# Breadboard.net
KiCad netlist of a schematic drawn in EAGLE
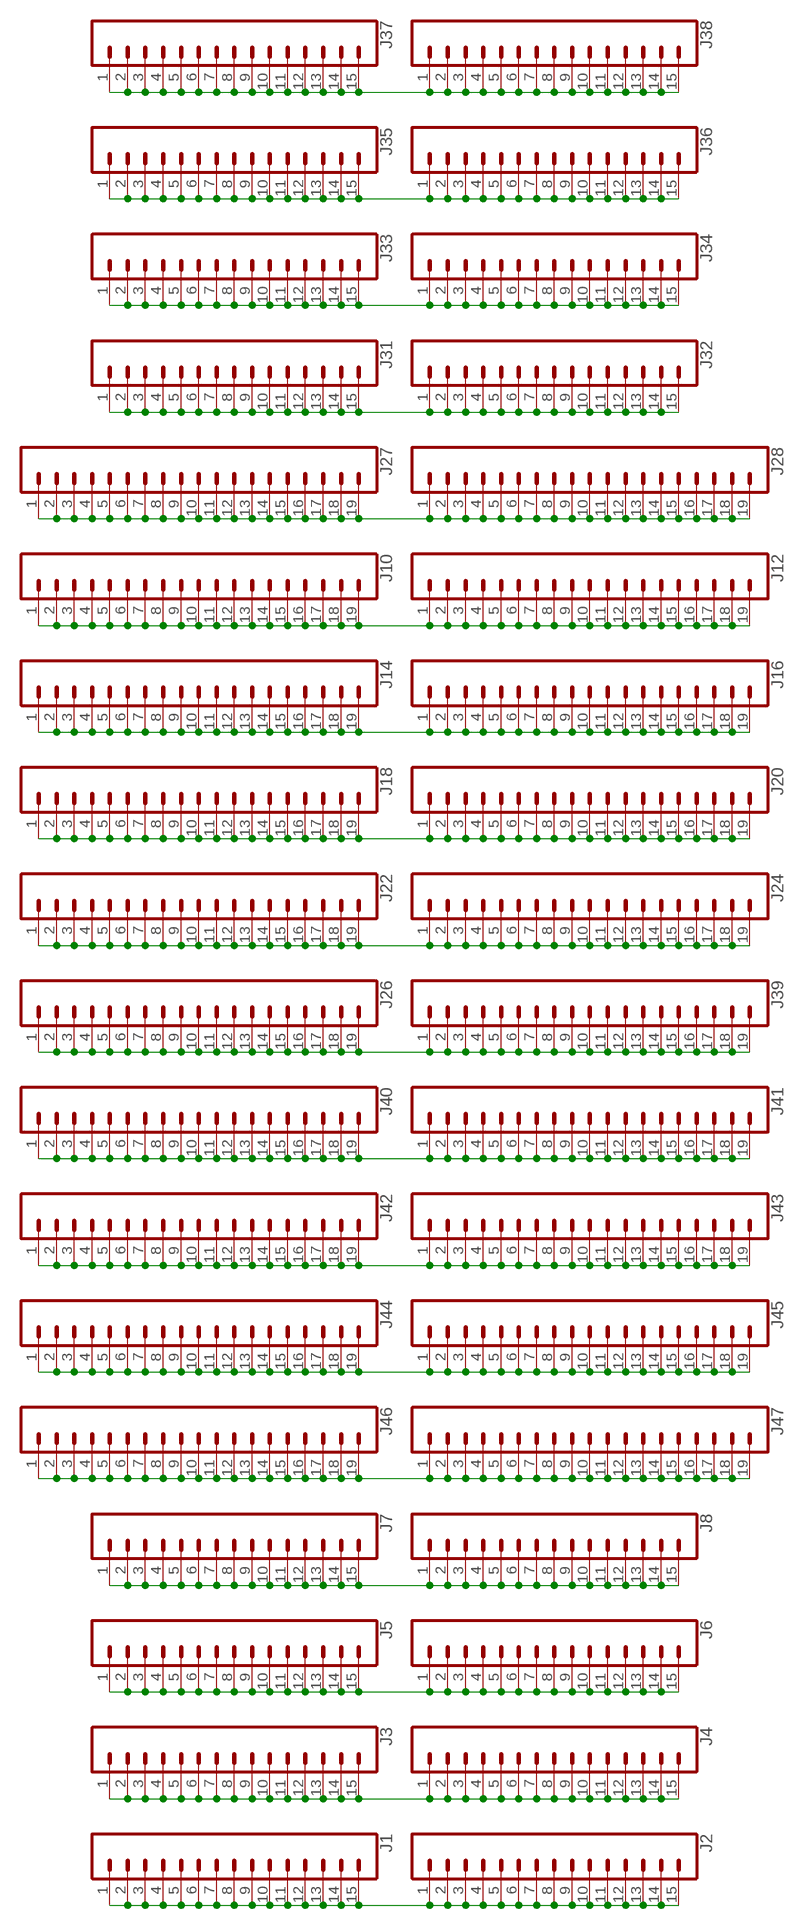
[diagram p0: schematic, sheet 1]

(export (version "E")
  (design (tool "Eeschema 10.0.6"))
  (components
    (comp (ref "J1")
      (value "CONN_15")
      (footprint "eagle-import:1X15")
      (libsource (lib "eagle-import") (part "CONN_15"))
    )
    (comp (ref "J2")
      (value "CONN_15")
      (footprint "eagle-import:1X15")
      (libsource (lib "eagle-import") (part "CONN_15"))
    )
    (comp (ref "J3")
      (value "CONN_15")
      (footprint "eagle-import:1X15")
      (libsource (lib "eagle-import") (part "CONN_15"))
    )
    (comp (ref "J4")
      (value "CONN_15")
      (footprint "eagle-import:1X15")
      (libsource (lib "eagle-import") (part "CONN_15"))
    )
    (comp (ref "J5")
      (value "CONN_15")
      (footprint "eagle-import:1X15")
      (libsource (lib "eagle-import") (part "CONN_15"))
    )
    (comp (ref "J6")
      (value "CONN_15")
      (footprint "eagle-import:1X15")
      (libsource (lib "eagle-import") (part "CONN_15"))
    )
    (comp (ref "J7")
      (value "CONN_15")
      (footprint "eagle-import:1X15")
      (libsource (lib "eagle-import") (part "CONN_15"))
    )
    (comp (ref "J8")
      (value "CONN_15")
      (footprint "eagle-import:1X15")
      (libsource (lib "eagle-import") (part "CONN_15"))
    )
    (comp (ref "J10")
      (value "CONN_19")
      (footprint "eagle-import:1X19")
      (libsource (lib "eagle-import") (part "CONN_19"))
    )
    (comp (ref "J12")
      (value "CONN_19")
      (footprint "eagle-import:1X19")
      (libsource (lib "eagle-import") (part "CONN_19"))
    )
    (comp (ref "J14")
      (value "CONN_19")
      (footprint "eagle-import:1X19")
      (libsource (lib "eagle-import") (part "CONN_19"))
    )
    (comp (ref "J16")
      (value "CONN_19")
      (footprint "eagle-import:1X19")
      (libsource (lib "eagle-import") (part "CONN_19"))
    )
    (comp (ref "J18")
      (value "CONN_19")
      (footprint "eagle-import:1X19")
      (libsource (lib "eagle-import") (part "CONN_19"))
    )
    (comp (ref "J20")
      (value "CONN_19")
      (footprint "eagle-import:1X19")
      (libsource (lib "eagle-import") (part "CONN_19"))
    )
    (comp (ref "J22")
      (value "CONN_19")
      (footprint "eagle-import:1X19")
      (libsource (lib "eagle-import") (part "CONN_19"))
    )
    (comp (ref "J24")
      (value "CONN_19")
      (footprint "eagle-import:1X19")
      (libsource (lib "eagle-import") (part "CONN_19"))
    )
    (comp (ref "J26")
      (value "CONN_19")
      (footprint "eagle-import:1X19")
      (libsource (lib "eagle-import") (part "CONN_19"))
    )
    (comp (ref "J27")
      (value "CONN_19")
      (footprint "eagle-import:1X19")
      (libsource (lib "eagle-import") (part "CONN_19"))
    )
    (comp (ref "J28")
      (value "CONN_19")
      (footprint "eagle-import:1X19")
      (libsource (lib "eagle-import") (part "CONN_19"))
    )
    (comp (ref "J31")
      (value "CONN_15")
      (footprint "eagle-import:1X15")
      (libsource (lib "eagle-import") (part "CONN_15"))
    )
    (comp (ref "J32")
      (value "CONN_15")
      (footprint "eagle-import:1X15")
      (libsource (lib "eagle-import") (part "CONN_15"))
    )
    (comp (ref "J33")
      (value "CONN_15")
      (footprint "eagle-import:1X15")
      (libsource (lib "eagle-import") (part "CONN_15"))
    )
    (comp (ref "J34")
      (value "CONN_15")
      (footprint "eagle-import:1X15")
      (libsource (lib "eagle-import") (part "CONN_15"))
    )
    (comp (ref "J35")
      (value "CONN_15")
      (footprint "eagle-import:1X15")
      (libsource (lib "eagle-import") (part "CONN_15"))
    )
    (comp (ref "J36")
      (value "CONN_15")
      (footprint "eagle-import:1X15")
      (libsource (lib "eagle-import") (part "CONN_15"))
    )
    (comp (ref "J37")
      (value "CONN_15")
      (footprint "eagle-import:1X15")
      (libsource (lib "eagle-import") (part "CONN_15"))
    )
    (comp (ref "J38")
      (value "CONN_15")
      (footprint "eagle-import:1X15")
      (libsource (lib "eagle-import") (part "CONN_15"))
    )
    (comp (ref "J39")
      (value "CONN_19")
      (footprint "eagle-import:1X19")
      (libsource (lib "eagle-import") (part "CONN_19"))
    )
    (comp (ref "J40")
      (value "CONN_19")
      (footprint "eagle-import:1X19")
      (libsource (lib "eagle-import") (part "CONN_19"))
    )
    (comp (ref "J41")
      (value "CONN_19")
      (footprint "eagle-import:1X19")
      (libsource (lib "eagle-import") (part "CONN_19"))
    )
    (comp (ref "J42")
      (value "CONN_19")
      (footprint "eagle-import:1X19")
      (libsource (lib "eagle-import") (part "CONN_19"))
    )
    (comp (ref "J43")
      (value "CONN_19")
      (footprint "eagle-import:1X19")
      (libsource (lib "eagle-import") (part "CONN_19"))
    )
    (comp (ref "J44")
      (value "CONN_19")
      (footprint "eagle-import:1X19")
      (libsource (lib "eagle-import") (part "CONN_19"))
    )
    (comp (ref "J45")
      (value "CONN_19")
      (footprint "eagle-import:1X19")
      (libsource (lib "eagle-import") (part "CONN_19"))
    )
    (comp (ref "J46")
      (value "CONN_19")
      (footprint "eagle-import:1X19")
      (libsource (lib "eagle-import") (part "CONN_19"))
    )
    (comp (ref "J47")
      (value "CONN_19")
      (footprint "eagle-import:1X19")
      (libsource (lib "eagle-import") (part "CONN_19"))
    )
  )
  (nets
    (net (code "1") (name "Net-(J1-Pad1)") (class "Default")
      (node (ref "J1") (pin "1") (pinfunction "1_1") (pintype "passive"))
      (node (ref "J1") (pin "10") (pinfunction "10_10") (pintype "passive"))
      (node (ref "J1") (pin "11") (pinfunction "11_11") (pintype "passive"))
      (node (ref "J1") (pin "12") (pinfunction "12_12") (pintype "passive"))
      (node (ref "J1") (pin "13") (pinfunction "13_13") (pintype "passive"))
      (node (ref "J1") (pin "14") (pinfunction "14_14") (pintype "passive"))
      (node (ref "J1") (pin "15") (pinfunction "15_15") (pintype "passive"))
      (node (ref "J1") (pin "2") (pinfunction "2_2") (pintype "passive"))
      (node (ref "J1") (pin "3") (pinfunction "3_3") (pintype "passive"))
      (node (ref "J1") (pin "4") (pinfunction "4_4") (pintype "passive"))
      (node (ref "J1") (pin "5") (pinfunction "5_5") (pintype "passive"))
      (node (ref "J1") (pin "6") (pinfunction "6_6") (pintype "passive"))
      (node (ref "J1") (pin "7") (pinfunction "7_7") (pintype "passive"))
      (node (ref "J1") (pin "8") (pinfunction "8_8") (pintype "passive"))
      (node (ref "J1") (pin "9") (pinfunction "9_9") (pintype "passive"))
      (node (ref "J2") (pin "1") (pinfunction "1_1") (pintype "passive"))
      (node (ref "J2") (pin "10") (pinfunction "10_10") (pintype "passive"))
      (node (ref "J2") (pin "11") (pinfunction "11_11") (pintype "passive"))
      (node (ref "J2") (pin "12") (pinfunction "12_12") (pintype "passive"))
      (node (ref "J2") (pin "13") (pinfunction "13_13") (pintype "passive"))
      (node (ref "J2") (pin "14") (pinfunction "14_14") (pintype "passive"))
      (node (ref "J2") (pin "15") (pinfunction "15_15") (pintype "passive"))
      (node (ref "J2") (pin "2") (pinfunction "2_2") (pintype "passive"))
      (node (ref "J2") (pin "3") (pinfunction "3_3") (pintype "passive"))
      (node (ref "J2") (pin "4") (pinfunction "4_4") (pintype "passive"))
      (node (ref "J2") (pin "5") (pinfunction "5_5") (pintype "passive"))
      (node (ref "J2") (pin "6") (pinfunction "6_6") (pintype "passive"))
      (node (ref "J2") (pin "7") (pinfunction "7_7") (pintype "passive"))
      (node (ref "J2") (pin "8") (pinfunction "8_8") (pintype "passive"))
      (node (ref "J2") (pin "9") (pinfunction "9_9") (pintype "passive"))
    )
    (net (code "2") (name "Net-(J3-Pad1)") (class "Default")
      (node (ref "J3") (pin "1") (pinfunction "1_1") (pintype "passive"))
      (node (ref "J3") (pin "10") (pinfunction "10_10") (pintype "passive"))
      (node (ref "J3") (pin "11") (pinfunction "11_11") (pintype "passive"))
      (node (ref "J3") (pin "12") (pinfunction "12_12") (pintype "passive"))
      (node (ref "J3") (pin "13") (pinfunction "13_13") (pintype "passive"))
      (node (ref "J3") (pin "14") (pinfunction "14_14") (pintype "passive"))
      (node (ref "J3") (pin "15") (pinfunction "15_15") (pintype "passive"))
      (node (ref "J3") (pin "2") (pinfunction "2_2") (pintype "passive"))
      (node (ref "J3") (pin "3") (pinfunction "3_3") (pintype "passive"))
      (node (ref "J3") (pin "4") (pinfunction "4_4") (pintype "passive"))
      (node (ref "J3") (pin "5") (pinfunction "5_5") (pintype "passive"))
      (node (ref "J3") (pin "6") (pinfunction "6_6") (pintype "passive"))
      (node (ref "J3") (pin "7") (pinfunction "7_7") (pintype "passive"))
      (node (ref "J3") (pin "8") (pinfunction "8_8") (pintype "passive"))
      (node (ref "J3") (pin "9") (pinfunction "9_9") (pintype "passive"))
      (node (ref "J4") (pin "1") (pinfunction "1_1") (pintype "passive"))
      (node (ref "J4") (pin "10") (pinfunction "10_10") (pintype "passive"))
      (node (ref "J4") (pin "11") (pinfunction "11_11") (pintype "passive"))
      (node (ref "J4") (pin "12") (pinfunction "12_12") (pintype "passive"))
      (node (ref "J4") (pin "13") (pinfunction "13_13") (pintype "passive"))
      (node (ref "J4") (pin "14") (pinfunction "14_14") (pintype "passive"))
      (node (ref "J4") (pin "15") (pinfunction "15_15") (pintype "passive"))
      (node (ref "J4") (pin "2") (pinfunction "2_2") (pintype "passive"))
      (node (ref "J4") (pin "3") (pinfunction "3_3") (pintype "passive"))
      (node (ref "J4") (pin "4") (pinfunction "4_4") (pintype "passive"))
      (node (ref "J4") (pin "5") (pinfunction "5_5") (pintype "passive"))
      (node (ref "J4") (pin "6") (pinfunction "6_6") (pintype "passive"))
      (node (ref "J4") (pin "7") (pinfunction "7_7") (pintype "passive"))
      (node (ref "J4") (pin "8") (pinfunction "8_8") (pintype "passive"))
      (node (ref "J4") (pin "9") (pinfunction "9_9") (pintype "passive"))
    )
    (net (code "3") (name "Net-(J5-Pad1)") (class "Default")
      (node (ref "J5") (pin "1") (pinfunction "1_1") (pintype "passive"))
      (node (ref "J5") (pin "10") (pinfunction "10_10") (pintype "passive"))
      (node (ref "J5") (pin "11") (pinfunction "11_11") (pintype "passive"))
      (node (ref "J5") (pin "12") (pinfunction "12_12") (pintype "passive"))
      (node (ref "J5") (pin "13") (pinfunction "13_13") (pintype "passive"))
      (node (ref "J5") (pin "14") (pinfunction "14_14") (pintype "passive"))
      (node (ref "J5") (pin "15") (pinfunction "15_15") (pintype "passive"))
      (node (ref "J5") (pin "2") (pinfunction "2_2") (pintype "passive"))
      (node (ref "J5") (pin "3") (pinfunction "3_3") (pintype "passive"))
      (node (ref "J5") (pin "4") (pinfunction "4_4") (pintype "passive"))
      (node (ref "J5") (pin "5") (pinfunction "5_5") (pintype "passive"))
      (node (ref "J5") (pin "6") (pinfunction "6_6") (pintype "passive"))
      (node (ref "J5") (pin "7") (pinfunction "7_7") (pintype "passive"))
      (node (ref "J5") (pin "8") (pinfunction "8_8") (pintype "passive"))
      (node (ref "J5") (pin "9") (pinfunction "9_9") (pintype "passive"))
      (node (ref "J6") (pin "1") (pinfunction "1_1") (pintype "passive"))
      (node (ref "J6") (pin "10") (pinfunction "10_10") (pintype "passive"))
      (node (ref "J6") (pin "11") (pinfunction "11_11") (pintype "passive"))
      (node (ref "J6") (pin "12") (pinfunction "12_12") (pintype "passive"))
      (node (ref "J6") (pin "13") (pinfunction "13_13") (pintype "passive"))
      (node (ref "J6") (pin "14") (pinfunction "14_14") (pintype "passive"))
      (node (ref "J6") (pin "15") (pinfunction "15_15") (pintype "passive"))
      (node (ref "J6") (pin "2") (pinfunction "2_2") (pintype "passive"))
      (node (ref "J6") (pin "3") (pinfunction "3_3") (pintype "passive"))
      (node (ref "J6") (pin "4") (pinfunction "4_4") (pintype "passive"))
      (node (ref "J6") (pin "5") (pinfunction "5_5") (pintype "passive"))
      (node (ref "J6") (pin "6") (pinfunction "6_6") (pintype "passive"))
      (node (ref "J6") (pin "7") (pinfunction "7_7") (pintype "passive"))
      (node (ref "J6") (pin "8") (pinfunction "8_8") (pintype "passive"))
      (node (ref "J6") (pin "9") (pinfunction "9_9") (pintype "passive"))
    )
    (net (code "4") (name "Net-(J7-Pad1)") (class "Default")
      (node (ref "J7") (pin "1") (pinfunction "1_1") (pintype "passive"))
      (node (ref "J7") (pin "10") (pinfunction "10_10") (pintype "passive"))
      (node (ref "J7") (pin "11") (pinfunction "11_11") (pintype "passive"))
      (node (ref "J7") (pin "12") (pinfunction "12_12") (pintype "passive"))
      (node (ref "J7") (pin "13") (pinfunction "13_13") (pintype "passive"))
      (node (ref "J7") (pin "14") (pinfunction "14_14") (pintype "passive"))
      (node (ref "J7") (pin "15") (pinfunction "15_15") (pintype "passive"))
      (node (ref "J7") (pin "2") (pinfunction "2_2") (pintype "passive"))
      (node (ref "J7") (pin "3") (pinfunction "3_3") (pintype "passive"))
      (node (ref "J7") (pin "4") (pinfunction "4_4") (pintype "passive"))
      (node (ref "J7") (pin "5") (pinfunction "5_5") (pintype "passive"))
      (node (ref "J7") (pin "6") (pinfunction "6_6") (pintype "passive"))
      (node (ref "J7") (pin "7") (pinfunction "7_7") (pintype "passive"))
      (node (ref "J7") (pin "8") (pinfunction "8_8") (pintype "passive"))
      (node (ref "J7") (pin "9") (pinfunction "9_9") (pintype "passive"))
      (node (ref "J8") (pin "1") (pinfunction "1_1") (pintype "passive"))
      (node (ref "J8") (pin "10") (pinfunction "10_10") (pintype "passive"))
      (node (ref "J8") (pin "11") (pinfunction "11_11") (pintype "passive"))
      (node (ref "J8") (pin "12") (pinfunction "12_12") (pintype "passive"))
      (node (ref "J8") (pin "13") (pinfunction "13_13") (pintype "passive"))
      (node (ref "J8") (pin "14") (pinfunction "14_14") (pintype "passive"))
      (node (ref "J8") (pin "15") (pinfunction "15_15") (pintype "passive"))
      (node (ref "J8") (pin "2") (pinfunction "2_2") (pintype "passive"))
      (node (ref "J8") (pin "3") (pinfunction "3_3") (pintype "passive"))
      (node (ref "J8") (pin "4") (pinfunction "4_4") (pintype "passive"))
      (node (ref "J8") (pin "5") (pinfunction "5_5") (pintype "passive"))
      (node (ref "J8") (pin "6") (pinfunction "6_6") (pintype "passive"))
      (node (ref "J8") (pin "7") (pinfunction "7_7") (pintype "passive"))
      (node (ref "J8") (pin "8") (pinfunction "8_8") (pintype "passive"))
      (node (ref "J8") (pin "9") (pinfunction "9_9") (pintype "passive"))
    )
    (net (code "5") (name "Net-(J10-Pad1)") (class "Default")
      (node (ref "J10") (pin "1") (pinfunction "1_1") (pintype "passive"))
      (node (ref "J10") (pin "10") (pinfunction "10_10") (pintype "passive"))
      (node (ref "J10") (pin "11") (pinfunction "11_11") (pintype "passive"))
      (node (ref "J10") (pin "12") (pinfunction "12_12") (pintype "passive"))
      (node (ref "J10") (pin "13") (pinfunction "13_13") (pintype "passive"))
      (node (ref "J10") (pin "14") (pinfunction "14_14") (pintype "passive"))
      (node (ref "J10") (pin "15") (pinfunction "15_15") (pintype "passive"))
      (node (ref "J10") (pin "16") (pinfunction "16_16") (pintype "passive"))
      (node (ref "J10") (pin "17") (pinfunction "17_17") (pintype "passive"))
      (node (ref "J10") (pin "18") (pinfunction "18_18") (pintype "passive"))
      (node (ref "J10") (pin "19") (pinfunction "19_19") (pintype "passive"))
      (node (ref "J10") (pin "2") (pinfunction "2_2") (pintype "passive"))
      (node (ref "J10") (pin "3") (pinfunction "3_3") (pintype "passive"))
      (node (ref "J10") (pin "4") (pinfunction "4_4") (pintype "passive"))
      (node (ref "J10") (pin "5") (pinfunction "5_5") (pintype "passive"))
      (node (ref "J10") (pin "6") (pinfunction "6_6") (pintype "passive"))
      (node (ref "J10") (pin "7") (pinfunction "7_7") (pintype "passive"))
      (node (ref "J10") (pin "8") (pinfunction "8_8") (pintype "passive"))
      (node (ref "J10") (pin "9") (pinfunction "9_9") (pintype "passive"))
      (node (ref "J12") (pin "1") (pinfunction "1_1") (pintype "passive"))
      (node (ref "J12") (pin "10") (pinfunction "10_10") (pintype "passive"))
      (node (ref "J12") (pin "11") (pinfunction "11_11") (pintype "passive"))
      (node (ref "J12") (pin "12") (pinfunction "12_12") (pintype "passive"))
      (node (ref "J12") (pin "13") (pinfunction "13_13") (pintype "passive"))
      (node (ref "J12") (pin "14") (pinfunction "14_14") (pintype "passive"))
      (node (ref "J12") (pin "15") (pinfunction "15_15") (pintype "passive"))
      (node (ref "J12") (pin "16") (pinfunction "16_16") (pintype "passive"))
      (node (ref "J12") (pin "17") (pinfunction "17_17") (pintype "passive"))
      (node (ref "J12") (pin "18") (pinfunction "18_18") (pintype "passive"))
      (node (ref "J12") (pin "19") (pinfunction "19_19") (pintype "passive"))
      (node (ref "J12") (pin "2") (pinfunction "2_2") (pintype "passive"))
      (node (ref "J12") (pin "3") (pinfunction "3_3") (pintype "passive"))
      (node (ref "J12") (pin "4") (pinfunction "4_4") (pintype "passive"))
      (node (ref "J12") (pin "5") (pinfunction "5_5") (pintype "passive"))
      (node (ref "J12") (pin "6") (pinfunction "6_6") (pintype "passive"))
      (node (ref "J12") (pin "7") (pinfunction "7_7") (pintype "passive"))
      (node (ref "J12") (pin "8") (pinfunction "8_8") (pintype "passive"))
      (node (ref "J12") (pin "9") (pinfunction "9_9") (pintype "passive"))
    )
    (net (code "6") (name "Net-(J14-Pad1)") (class "Default")
      (node (ref "J14") (pin "1") (pinfunction "1_1") (pintype "passive"))
      (node (ref "J14") (pin "10") (pinfunction "10_10") (pintype "passive"))
      (node (ref "J14") (pin "11") (pinfunction "11_11") (pintype "passive"))
      (node (ref "J14") (pin "12") (pinfunction "12_12") (pintype "passive"))
      (node (ref "J14") (pin "13") (pinfunction "13_13") (pintype "passive"))
      (node (ref "J14") (pin "14") (pinfunction "14_14") (pintype "passive"))
      (node (ref "J14") (pin "15") (pinfunction "15_15") (pintype "passive"))
      (node (ref "J14") (pin "16") (pinfunction "16_16") (pintype "passive"))
      (node (ref "J14") (pin "17") (pinfunction "17_17") (pintype "passive"))
      (node (ref "J14") (pin "18") (pinfunction "18_18") (pintype "passive"))
      (node (ref "J14") (pin "19") (pinfunction "19_19") (pintype "passive"))
      (node (ref "J14") (pin "2") (pinfunction "2_2") (pintype "passive"))
      (node (ref "J14") (pin "3") (pinfunction "3_3") (pintype "passive"))
      (node (ref "J14") (pin "4") (pinfunction "4_4") (pintype "passive"))
      (node (ref "J14") (pin "5") (pinfunction "5_5") (pintype "passive"))
      (node (ref "J14") (pin "6") (pinfunction "6_6") (pintype "passive"))
      (node (ref "J14") (pin "7") (pinfunction "7_7") (pintype "passive"))
      (node (ref "J14") (pin "8") (pinfunction "8_8") (pintype "passive"))
      (node (ref "J14") (pin "9") (pinfunction "9_9") (pintype "passive"))
      (node (ref "J16") (pin "1") (pinfunction "1_1") (pintype "passive"))
      (node (ref "J16") (pin "10") (pinfunction "10_10") (pintype "passive"))
      (node (ref "J16") (pin "11") (pinfunction "11_11") (pintype "passive"))
      (node (ref "J16") (pin "12") (pinfunction "12_12") (pintype "passive"))
      (node (ref "J16") (pin "13") (pinfunction "13_13") (pintype "passive"))
      (node (ref "J16") (pin "14") (pinfunction "14_14") (pintype "passive"))
      (node (ref "J16") (pin "15") (pinfunction "15_15") (pintype "passive"))
      (node (ref "J16") (pin "16") (pinfunction "16_16") (pintype "passive"))
      (node (ref "J16") (pin "17") (pinfunction "17_17") (pintype "passive"))
      (node (ref "J16") (pin "18") (pinfunction "18_18") (pintype "passive"))
      (node (ref "J16") (pin "19") (pinfunction "19_19") (pintype "passive"))
      (node (ref "J16") (pin "2") (pinfunction "2_2") (pintype "passive"))
      (node (ref "J16") (pin "3") (pinfunction "3_3") (pintype "passive"))
      (node (ref "J16") (pin "4") (pinfunction "4_4") (pintype "passive"))
      (node (ref "J16") (pin "5") (pinfunction "5_5") (pintype "passive"))
      (node (ref "J16") (pin "6") (pinfunction "6_6") (pintype "passive"))
      (node (ref "J16") (pin "7") (pinfunction "7_7") (pintype "passive"))
      (node (ref "J16") (pin "8") (pinfunction "8_8") (pintype "passive"))
      (node (ref "J16") (pin "9") (pinfunction "9_9") (pintype "passive"))
    )
    (net (code "7") (name "Net-(J18-Pad1)") (class "Default")
      (node (ref "J18") (pin "1") (pinfunction "1_1") (pintype "passive"))
      (node (ref "J18") (pin "10") (pinfunction "10_10") (pintype "passive"))
      (node (ref "J18") (pin "11") (pinfunction "11_11") (pintype "passive"))
      (node (ref "J18") (pin "12") (pinfunction "12_12") (pintype "passive"))
      (node (ref "J18") (pin "13") (pinfunction "13_13") (pintype "passive"))
      (node (ref "J18") (pin "14") (pinfunction "14_14") (pintype "passive"))
      (node (ref "J18") (pin "15") (pinfunction "15_15") (pintype "passive"))
      (node (ref "J18") (pin "16") (pinfunction "16_16") (pintype "passive"))
      (node (ref "J18") (pin "17") (pinfunction "17_17") (pintype "passive"))
      (node (ref "J18") (pin "18") (pinfunction "18_18") (pintype "passive"))
      (node (ref "J18") (pin "19") (pinfunction "19_19") (pintype "passive"))
      (node (ref "J18") (pin "2") (pinfunction "2_2") (pintype "passive"))
      (node (ref "J18") (pin "3") (pinfunction "3_3") (pintype "passive"))
      (node (ref "J18") (pin "4") (pinfunction "4_4") (pintype "passive"))
      (node (ref "J18") (pin "5") (pinfunction "5_5") (pintype "passive"))
      (node (ref "J18") (pin "6") (pinfunction "6_6") (pintype "passive"))
      (node (ref "J18") (pin "7") (pinfunction "7_7") (pintype "passive"))
      (node (ref "J18") (pin "8") (pinfunction "8_8") (pintype "passive"))
      (node (ref "J18") (pin "9") (pinfunction "9_9") (pintype "passive"))
      (node (ref "J20") (pin "1") (pinfunction "1_1") (pintype "passive"))
      (node (ref "J20") (pin "10") (pinfunction "10_10") (pintype "passive"))
      (node (ref "J20") (pin "11") (pinfunction "11_11") (pintype "passive"))
      (node (ref "J20") (pin "12") (pinfunction "12_12") (pintype "passive"))
      (node (ref "J20") (pin "13") (pinfunction "13_13") (pintype "passive"))
      (node (ref "J20") (pin "14") (pinfunction "14_14") (pintype "passive"))
      (node (ref "J20") (pin "15") (pinfunction "15_15") (pintype "passive"))
      (node (ref "J20") (pin "16") (pinfunction "16_16") (pintype "passive"))
      (node (ref "J20") (pin "17") (pinfunction "17_17") (pintype "passive"))
      (node (ref "J20") (pin "18") (pinfunction "18_18") (pintype "passive"))
      (node (ref "J20") (pin "19") (pinfunction "19_19") (pintype "passive"))
      (node (ref "J20") (pin "2") (pinfunction "2_2") (pintype "passive"))
      (node (ref "J20") (pin "3") (pinfunction "3_3") (pintype "passive"))
      (node (ref "J20") (pin "4") (pinfunction "4_4") (pintype "passive"))
      (node (ref "J20") (pin "5") (pinfunction "5_5") (pintype "passive"))
      (node (ref "J20") (pin "6") (pinfunction "6_6") (pintype "passive"))
      (node (ref "J20") (pin "7") (pinfunction "7_7") (pintype "passive"))
      (node (ref "J20") (pin "8") (pinfunction "8_8") (pintype "passive"))
      (node (ref "J20") (pin "9") (pinfunction "9_9") (pintype "passive"))
    )
    (net (code "8") (name "Net-(J22-Pad1)") (class "Default")
      (node (ref "J22") (pin "1") (pinfunction "1_1") (pintype "passive"))
      (node (ref "J22") (pin "10") (pinfunction "10_10") (pintype "passive"))
      (node (ref "J22") (pin "11") (pinfunction "11_11") (pintype "passive"))
      (node (ref "J22") (pin "12") (pinfunction "12_12") (pintype "passive"))
      (node (ref "J22") (pin "13") (pinfunction "13_13") (pintype "passive"))
      (node (ref "J22") (pin "14") (pinfunction "14_14") (pintype "passive"))
      (node (ref "J22") (pin "15") (pinfunction "15_15") (pintype "passive"))
      (node (ref "J22") (pin "16") (pinfunction "16_16") (pintype "passive"))
      (node (ref "J22") (pin "17") (pinfunction "17_17") (pintype "passive"))
      (node (ref "J22") (pin "18") (pinfunction "18_18") (pintype "passive"))
      (node (ref "J22") (pin "19") (pinfunction "19_19") (pintype "passive"))
      (node (ref "J22") (pin "2") (pinfunction "2_2") (pintype "passive"))
      (node (ref "J22") (pin "3") (pinfunction "3_3") (pintype "passive"))
      (node (ref "J22") (pin "4") (pinfunction "4_4") (pintype "passive"))
      (node (ref "J22") (pin "5") (pinfunction "5_5") (pintype "passive"))
      (node (ref "J22") (pin "6") (pinfunction "6_6") (pintype "passive"))
      (node (ref "J22") (pin "7") (pinfunction "7_7") (pintype "passive"))
      (node (ref "J22") (pin "8") (pinfunction "8_8") (pintype "passive"))
      (node (ref "J22") (pin "9") (pinfunction "9_9") (pintype "passive"))
      (node (ref "J24") (pin "1") (pinfunction "1_1") (pintype "passive"))
      (node (ref "J24") (pin "10") (pinfunction "10_10") (pintype "passive"))
      (node (ref "J24") (pin "11") (pinfunction "11_11") (pintype "passive"))
      (node (ref "J24") (pin "12") (pinfunction "12_12") (pintype "passive"))
      (node (ref "J24") (pin "13") (pinfunction "13_13") (pintype "passive"))
      (node (ref "J24") (pin "14") (pinfunction "14_14") (pintype "passive"))
      (node (ref "J24") (pin "15") (pinfunction "15_15") (pintype "passive"))
      (node (ref "J24") (pin "16") (pinfunction "16_16") (pintype "passive"))
      (node (ref "J24") (pin "17") (pinfunction "17_17") (pintype "passive"))
      (node (ref "J24") (pin "18") (pinfunction "18_18") (pintype "passive"))
      (node (ref "J24") (pin "19") (pinfunction "19_19") (pintype "passive"))
      (node (ref "J24") (pin "2") (pinfunction "2_2") (pintype "passive"))
      (node (ref "J24") (pin "3") (pinfunction "3_3") (pintype "passive"))
      (node (ref "J24") (pin "4") (pinfunction "4_4") (pintype "passive"))
      (node (ref "J24") (pin "5") (pinfunction "5_5") (pintype "passive"))
      (node (ref "J24") (pin "6") (pinfunction "6_6") (pintype "passive"))
      (node (ref "J24") (pin "7") (pinfunction "7_7") (pintype "passive"))
      (node (ref "J24") (pin "8") (pinfunction "8_8") (pintype "passive"))
      (node (ref "J24") (pin "9") (pinfunction "9_9") (pintype "passive"))
    )
    (net (code "9") (name "Net-(J26-Pad1)") (class "Default")
      (node (ref "J26") (pin "1") (pinfunction "1_1") (pintype "passive"))
      (node (ref "J26") (pin "10") (pinfunction "10_10") (pintype "passive"))
      (node (ref "J26") (pin "11") (pinfunction "11_11") (pintype "passive"))
      (node (ref "J26") (pin "12") (pinfunction "12_12") (pintype "passive"))
      (node (ref "J26") (pin "13") (pinfunction "13_13") (pintype "passive"))
      (node (ref "J26") (pin "14") (pinfunction "14_14") (pintype "passive"))
      (node (ref "J26") (pin "15") (pinfunction "15_15") (pintype "passive"))
      (node (ref "J26") (pin "16") (pinfunction "16_16") (pintype "passive"))
      (node (ref "J26") (pin "17") (pinfunction "17_17") (pintype "passive"))
      (node (ref "J26") (pin "18") (pinfunction "18_18") (pintype "passive"))
      (node (ref "J26") (pin "19") (pinfunction "19_19") (pintype "passive"))
      (node (ref "J26") (pin "2") (pinfunction "2_2") (pintype "passive"))
      (node (ref "J26") (pin "3") (pinfunction "3_3") (pintype "passive"))
      (node (ref "J26") (pin "4") (pinfunction "4_4") (pintype "passive"))
      (node (ref "J26") (pin "5") (pinfunction "5_5") (pintype "passive"))
      (node (ref "J26") (pin "6") (pinfunction "6_6") (pintype "passive"))
      (node (ref "J26") (pin "7") (pinfunction "7_7") (pintype "passive"))
      (node (ref "J26") (pin "8") (pinfunction "8_8") (pintype "passive"))
      (node (ref "J26") (pin "9") (pinfunction "9_9") (pintype "passive"))
      (node (ref "J39") (pin "1") (pinfunction "1_1") (pintype "passive"))
      (node (ref "J39") (pin "10") (pinfunction "10_10") (pintype "passive"))
      (node (ref "J39") (pin "11") (pinfunction "11_11") (pintype "passive"))
      (node (ref "J39") (pin "12") (pinfunction "12_12") (pintype "passive"))
      (node (ref "J39") (pin "13") (pinfunction "13_13") (pintype "passive"))
      (node (ref "J39") (pin "14") (pinfunction "14_14") (pintype "passive"))
      (node (ref "J39") (pin "15") (pinfunction "15_15") (pintype "passive"))
      (node (ref "J39") (pin "16") (pinfunction "16_16") (pintype "passive"))
      (node (ref "J39") (pin "17") (pinfunction "17_17") (pintype "passive"))
      (node (ref "J39") (pin "18") (pinfunction "18_18") (pintype "passive"))
      (node (ref "J39") (pin "19") (pinfunction "19_19") (pintype "passive"))
      (node (ref "J39") (pin "2") (pinfunction "2_2") (pintype "passive"))
      (node (ref "J39") (pin "3") (pinfunction "3_3") (pintype "passive"))
      (node (ref "J39") (pin "4") (pinfunction "4_4") (pintype "passive"))
      (node (ref "J39") (pin "5") (pinfunction "5_5") (pintype "passive"))
      (node (ref "J39") (pin "6") (pinfunction "6_6") (pintype "passive"))
      (node (ref "J39") (pin "7") (pinfunction "7_7") (pintype "passive"))
      (node (ref "J39") (pin "8") (pinfunction "8_8") (pintype "passive"))
      (node (ref "J39") (pin "9") (pinfunction "9_9") (pintype "passive"))
    )
    (net (code "10") (name "Net-(J27-Pad1)") (class "Default")
      (node (ref "J27") (pin "1") (pinfunction "1_1") (pintype "passive"))
      (node (ref "J27") (pin "10") (pinfunction "10_10") (pintype "passive"))
      (node (ref "J27") (pin "11") (pinfunction "11_11") (pintype "passive"))
      (node (ref "J27") (pin "12") (pinfunction "12_12") (pintype "passive"))
      (node (ref "J27") (pin "13") (pinfunction "13_13") (pintype "passive"))
      (node (ref "J27") (pin "14") (pinfunction "14_14") (pintype "passive"))
      (node (ref "J27") (pin "15") (pinfunction "15_15") (pintype "passive"))
      (node (ref "J27") (pin "16") (pinfunction "16_16") (pintype "passive"))
      (node (ref "J27") (pin "17") (pinfunction "17_17") (pintype "passive"))
      (node (ref "J27") (pin "18") (pinfunction "18_18") (pintype "passive"))
      (node (ref "J27") (pin "19") (pinfunction "19_19") (pintype "passive"))
      (node (ref "J27") (pin "2") (pinfunction "2_2") (pintype "passive"))
      (node (ref "J27") (pin "3") (pinfunction "3_3") (pintype "passive"))
      (node (ref "J27") (pin "4") (pinfunction "4_4") (pintype "passive"))
      (node (ref "J27") (pin "5") (pinfunction "5_5") (pintype "passive"))
      (node (ref "J27") (pin "6") (pinfunction "6_6") (pintype "passive"))
      (node (ref "J27") (pin "7") (pinfunction "7_7") (pintype "passive"))
      (node (ref "J27") (pin "8") (pinfunction "8_8") (pintype "passive"))
      (node (ref "J27") (pin "9") (pinfunction "9_9") (pintype "passive"))
      (node (ref "J28") (pin "1") (pinfunction "1_1") (pintype "passive"))
      (node (ref "J28") (pin "10") (pinfunction "10_10") (pintype "passive"))
      (node (ref "J28") (pin "11") (pinfunction "11_11") (pintype "passive"))
      (node (ref "J28") (pin "12") (pinfunction "12_12") (pintype "passive"))
      (node (ref "J28") (pin "13") (pinfunction "13_13") (pintype "passive"))
      (node (ref "J28") (pin "14") (pinfunction "14_14") (pintype "passive"))
      (node (ref "J28") (pin "15") (pinfunction "15_15") (pintype "passive"))
      (node (ref "J28") (pin "16") (pinfunction "16_16") (pintype "passive"))
      (node (ref "J28") (pin "17") (pinfunction "17_17") (pintype "passive"))
      (node (ref "J28") (pin "18") (pinfunction "18_18") (pintype "passive"))
      (node (ref "J28") (pin "19") (pinfunction "19_19") (pintype "passive"))
      (node (ref "J28") (pin "2") (pinfunction "2_2") (pintype "passive"))
      (node (ref "J28") (pin "3") (pinfunction "3_3") (pintype "passive"))
      (node (ref "J28") (pin "4") (pinfunction "4_4") (pintype "passive"))
      (node (ref "J28") (pin "5") (pinfunction "5_5") (pintype "passive"))
      (node (ref "J28") (pin "6") (pinfunction "6_6") (pintype "passive"))
      (node (ref "J28") (pin "7") (pinfunction "7_7") (pintype "passive"))
      (node (ref "J28") (pin "8") (pinfunction "8_8") (pintype "passive"))
      (node (ref "J28") (pin "9") (pinfunction "9_9") (pintype "passive"))
    )
    (net (code "11") (name "Net-(J31-Pad1)") (class "Default")
      (node (ref "J31") (pin "1") (pinfunction "1_1") (pintype "passive"))
      (node (ref "J31") (pin "10") (pinfunction "10_10") (pintype "passive"))
      (node (ref "J31") (pin "11") (pinfunction "11_11") (pintype "passive"))
      (node (ref "J31") (pin "12") (pinfunction "12_12") (pintype "passive"))
      (node (ref "J31") (pin "13") (pinfunction "13_13") (pintype "passive"))
      (node (ref "J31") (pin "14") (pinfunction "14_14") (pintype "passive"))
      (node (ref "J31") (pin "15") (pinfunction "15_15") (pintype "passive"))
      (node (ref "J31") (pin "2") (pinfunction "2_2") (pintype "passive"))
      (node (ref "J31") (pin "3") (pinfunction "3_3") (pintype "passive"))
      (node (ref "J31") (pin "4") (pinfunction "4_4") (pintype "passive"))
      (node (ref "J31") (pin "5") (pinfunction "5_5") (pintype "passive"))
      (node (ref "J31") (pin "6") (pinfunction "6_6") (pintype "passive"))
      (node (ref "J31") (pin "7") (pinfunction "7_7") (pintype "passive"))
      (node (ref "J31") (pin "8") (pinfunction "8_8") (pintype "passive"))
      (node (ref "J31") (pin "9") (pinfunction "9_9") (pintype "passive"))
      (node (ref "J32") (pin "1") (pinfunction "1_1") (pintype "passive"))
      (node (ref "J32") (pin "10") (pinfunction "10_10") (pintype "passive"))
      (node (ref "J32") (pin "11") (pinfunction "11_11") (pintype "passive"))
      (node (ref "J32") (pin "12") (pinfunction "12_12") (pintype "passive"))
      (node (ref "J32") (pin "13") (pinfunction "13_13") (pintype "passive"))
      (node (ref "J32") (pin "14") (pinfunction "14_14") (pintype "passive"))
      (node (ref "J32") (pin "15") (pinfunction "15_15") (pintype "passive"))
      (node (ref "J32") (pin "2") (pinfunction "2_2") (pintype "passive"))
      (node (ref "J32") (pin "3") (pinfunction "3_3") (pintype "passive"))
      (node (ref "J32") (pin "4") (pinfunction "4_4") (pintype "passive"))
      (node (ref "J32") (pin "5") (pinfunction "5_5") (pintype "passive"))
      (node (ref "J32") (pin "6") (pinfunction "6_6") (pintype "passive"))
      (node (ref "J32") (pin "7") (pinfunction "7_7") (pintype "passive"))
      (node (ref "J32") (pin "8") (pinfunction "8_8") (pintype "passive"))
      (node (ref "J32") (pin "9") (pinfunction "9_9") (pintype "passive"))
    )
    (net (code "12") (name "Net-(J33-Pad1)") (class "Default")
      (node (ref "J33") (pin "1") (pinfunction "1_1") (pintype "passive"))
      (node (ref "J33") (pin "10") (pinfunction "10_10") (pintype "passive"))
      (node (ref "J33") (pin "11") (pinfunction "11_11") (pintype "passive"))
      (node (ref "J33") (pin "12") (pinfunction "12_12") (pintype "passive"))
      (node (ref "J33") (pin "13") (pinfunction "13_13") (pintype "passive"))
      (node (ref "J33") (pin "14") (pinfunction "14_14") (pintype "passive"))
      (node (ref "J33") (pin "15") (pinfunction "15_15") (pintype "passive"))
      (node (ref "J33") (pin "2") (pinfunction "2_2") (pintype "passive"))
      (node (ref "J33") (pin "3") (pinfunction "3_3") (pintype "passive"))
      (node (ref "J33") (pin "4") (pinfunction "4_4") (pintype "passive"))
      (node (ref "J33") (pin "5") (pinfunction "5_5") (pintype "passive"))
      (node (ref "J33") (pin "6") (pinfunction "6_6") (pintype "passive"))
      (node (ref "J33") (pin "7") (pinfunction "7_7") (pintype "passive"))
      (node (ref "J33") (pin "8") (pinfunction "8_8") (pintype "passive"))
      (node (ref "J33") (pin "9") (pinfunction "9_9") (pintype "passive"))
      (node (ref "J34") (pin "1") (pinfunction "1_1") (pintype "passive"))
      (node (ref "J34") (pin "10") (pinfunction "10_10") (pintype "passive"))
      (node (ref "J34") (pin "11") (pinfunction "11_11") (pintype "passive"))
      (node (ref "J34") (pin "12") (pinfunction "12_12") (pintype "passive"))
      (node (ref "J34") (pin "13") (pinfunction "13_13") (pintype "passive"))
      (node (ref "J34") (pin "14") (pinfunction "14_14") (pintype "passive"))
      (node (ref "J34") (pin "15") (pinfunction "15_15") (pintype "passive"))
      (node (ref "J34") (pin "2") (pinfunction "2_2") (pintype "passive"))
      (node (ref "J34") (pin "3") (pinfunction "3_3") (pintype "passive"))
      (node (ref "J34") (pin "4") (pinfunction "4_4") (pintype "passive"))
      (node (ref "J34") (pin "5") (pinfunction "5_5") (pintype "passive"))
      (node (ref "J34") (pin "6") (pinfunction "6_6") (pintype "passive"))
      (node (ref "J34") (pin "7") (pinfunction "7_7") (pintype "passive"))
      (node (ref "J34") (pin "8") (pinfunction "8_8") (pintype "passive"))
      (node (ref "J34") (pin "9") (pinfunction "9_9") (pintype "passive"))
    )
    (net (code "13") (name "Net-(J35-Pad1)") (class "Default")
      (node (ref "J35") (pin "1") (pinfunction "1_1") (pintype "passive"))
      (node (ref "J35") (pin "10") (pinfunction "10_10") (pintype "passive"))
      (node (ref "J35") (pin "11") (pinfunction "11_11") (pintype "passive"))
      (node (ref "J35") (pin "12") (pinfunction "12_12") (pintype "passive"))
      (node (ref "J35") (pin "13") (pinfunction "13_13") (pintype "passive"))
      (node (ref "J35") (pin "14") (pinfunction "14_14") (pintype "passive"))
      (node (ref "J35") (pin "15") (pinfunction "15_15") (pintype "passive"))
      (node (ref "J35") (pin "2") (pinfunction "2_2") (pintype "passive"))
      (node (ref "J35") (pin "3") (pinfunction "3_3") (pintype "passive"))
      (node (ref "J35") (pin "4") (pinfunction "4_4") (pintype "passive"))
      (node (ref "J35") (pin "5") (pinfunction "5_5") (pintype "passive"))
      (node (ref "J35") (pin "6") (pinfunction "6_6") (pintype "passive"))
      (node (ref "J35") (pin "7") (pinfunction "7_7") (pintype "passive"))
      (node (ref "J35") (pin "8") (pinfunction "8_8") (pintype "passive"))
      (node (ref "J35") (pin "9") (pinfunction "9_9") (pintype "passive"))
      (node (ref "J36") (pin "1") (pinfunction "1_1") (pintype "passive"))
      (node (ref "J36") (pin "10") (pinfunction "10_10") (pintype "passive"))
      (node (ref "J36") (pin "11") (pinfunction "11_11") (pintype "passive"))
      (node (ref "J36") (pin "12") (pinfunction "12_12") (pintype "passive"))
      (node (ref "J36") (pin "13") (pinfunction "13_13") (pintype "passive"))
      (node (ref "J36") (pin "14") (pinfunction "14_14") (pintype "passive"))
      (node (ref "J36") (pin "15") (pinfunction "15_15") (pintype "passive"))
      (node (ref "J36") (pin "2") (pinfunction "2_2") (pintype "passive"))
      (node (ref "J36") (pin "3") (pinfunction "3_3") (pintype "passive"))
      (node (ref "J36") (pin "4") (pinfunction "4_4") (pintype "passive"))
      (node (ref "J36") (pin "5") (pinfunction "5_5") (pintype "passive"))
      (node (ref "J36") (pin "6") (pinfunction "6_6") (pintype "passive"))
      (node (ref "J36") (pin "7") (pinfunction "7_7") (pintype "passive"))
      (node (ref "J36") (pin "8") (pinfunction "8_8") (pintype "passive"))
      (node (ref "J36") (pin "9") (pinfunction "9_9") (pintype "passive"))
    )
    (net (code "14") (name "Net-(J37-Pad1)") (class "Default")
      (node (ref "J37") (pin "1") (pinfunction "1_1") (pintype "passive"))
      (node (ref "J37") (pin "10") (pinfunction "10_10") (pintype "passive"))
      (node (ref "J37") (pin "11") (pinfunction "11_11") (pintype "passive"))
      (node (ref "J37") (pin "12") (pinfunction "12_12") (pintype "passive"))
      (node (ref "J37") (pin "13") (pinfunction "13_13") (pintype "passive"))
      (node (ref "J37") (pin "14") (pinfunction "14_14") (pintype "passive"))
      (node (ref "J37") (pin "15") (pinfunction "15_15") (pintype "passive"))
      (node (ref "J37") (pin "2") (pinfunction "2_2") (pintype "passive"))
      (node (ref "J37") (pin "3") (pinfunction "3_3") (pintype "passive"))
      (node (ref "J37") (pin "4") (pinfunction "4_4") (pintype "passive"))
      (node (ref "J37") (pin "5") (pinfunction "5_5") (pintype "passive"))
      (node (ref "J37") (pin "6") (pinfunction "6_6") (pintype "passive"))
      (node (ref "J37") (pin "7") (pinfunction "7_7") (pintype "passive"))
      (node (ref "J37") (pin "8") (pinfunction "8_8") (pintype "passive"))
      (node (ref "J37") (pin "9") (pinfunction "9_9") (pintype "passive"))
      (node (ref "J38") (pin "1") (pinfunction "1_1") (pintype "passive"))
      (node (ref "J38") (pin "10") (pinfunction "10_10") (pintype "passive"))
      (node (ref "J38") (pin "11") (pinfunction "11_11") (pintype "passive"))
      (node (ref "J38") (pin "12") (pinfunction "12_12") (pintype "passive"))
      (node (ref "J38") (pin "13") (pinfunction "13_13") (pintype "passive"))
      (node (ref "J38") (pin "14") (pinfunction "14_14") (pintype "passive"))
      (node (ref "J38") (pin "15") (pinfunction "15_15") (pintype "passive"))
      (node (ref "J38") (pin "2") (pinfunction "2_2") (pintype "passive"))
      (node (ref "J38") (pin "3") (pinfunction "3_3") (pintype "passive"))
      (node (ref "J38") (pin "4") (pinfunction "4_4") (pintype "passive"))
      (node (ref "J38") (pin "5") (pinfunction "5_5") (pintype "passive"))
      (node (ref "J38") (pin "6") (pinfunction "6_6") (pintype "passive"))
      (node (ref "J38") (pin "7") (pinfunction "7_7") (pintype "passive"))
      (node (ref "J38") (pin "8") (pinfunction "8_8") (pintype "passive"))
      (node (ref "J38") (pin "9") (pinfunction "9_9") (pintype "passive"))
    )
    (net (code "15") (name "Net-(J40-Pad1)") (class "Default")
      (node (ref "J40") (pin "1") (pinfunction "1_1") (pintype "passive"))
      (node (ref "J40") (pin "10") (pinfunction "10_10") (pintype "passive"))
      (node (ref "J40") (pin "11") (pinfunction "11_11") (pintype "passive"))
      (node (ref "J40") (pin "12") (pinfunction "12_12") (pintype "passive"))
      (node (ref "J40") (pin "13") (pinfunction "13_13") (pintype "passive"))
      (node (ref "J40") (pin "14") (pinfunction "14_14") (pintype "passive"))
      (node (ref "J40") (pin "15") (pinfunction "15_15") (pintype "passive"))
      (node (ref "J40") (pin "16") (pinfunction "16_16") (pintype "passive"))
      (node (ref "J40") (pin "17") (pinfunction "17_17") (pintype "passive"))
      (node (ref "J40") (pin "18") (pinfunction "18_18") (pintype "passive"))
      (node (ref "J40") (pin "19") (pinfunction "19_19") (pintype "passive"))
      (node (ref "J40") (pin "2") (pinfunction "2_2") (pintype "passive"))
      (node (ref "J40") (pin "3") (pinfunction "3_3") (pintype "passive"))
      (node (ref "J40") (pin "4") (pinfunction "4_4") (pintype "passive"))
      (node (ref "J40") (pin "5") (pinfunction "5_5") (pintype "passive"))
      (node (ref "J40") (pin "6") (pinfunction "6_6") (pintype "passive"))
      (node (ref "J40") (pin "7") (pinfunction "7_7") (pintype "passive"))
      (node (ref "J40") (pin "8") (pinfunction "8_8") (pintype "passive"))
      (node (ref "J40") (pin "9") (pinfunction "9_9") (pintype "passive"))
      (node (ref "J41") (pin "1") (pinfunction "1_1") (pintype "passive"))
      (node (ref "J41") (pin "10") (pinfunction "10_10") (pintype "passive"))
      (node (ref "J41") (pin "11") (pinfunction "11_11") (pintype "passive"))
      (node (ref "J41") (pin "12") (pinfunction "12_12") (pintype "passive"))
      (node (ref "J41") (pin "13") (pinfunction "13_13") (pintype "passive"))
      (node (ref "J41") (pin "14") (pinfunction "14_14") (pintype "passive"))
      (node (ref "J41") (pin "15") (pinfunction "15_15") (pintype "passive"))
      (node (ref "J41") (pin "16") (pinfunction "16_16") (pintype "passive"))
      (node (ref "J41") (pin "17") (pinfunction "17_17") (pintype "passive"))
      (node (ref "J41") (pin "18") (pinfunction "18_18") (pintype "passive"))
      (node (ref "J41") (pin "19") (pinfunction "19_19") (pintype "passive"))
      (node (ref "J41") (pin "2") (pinfunction "2_2") (pintype "passive"))
      (node (ref "J41") (pin "3") (pinfunction "3_3") (pintype "passive"))
      (node (ref "J41") (pin "4") (pinfunction "4_4") (pintype "passive"))
      (node (ref "J41") (pin "5") (pinfunction "5_5") (pintype "passive"))
      (node (ref "J41") (pin "6") (pinfunction "6_6") (pintype "passive"))
      (node (ref "J41") (pin "7") (pinfunction "7_7") (pintype "passive"))
      (node (ref "J41") (pin "8") (pinfunction "8_8") (pintype "passive"))
      (node (ref "J41") (pin "9") (pinfunction "9_9") (pintype "passive"))
    )
    (net (code "16") (name "Net-(J42-Pad1)") (class "Default")
      (node (ref "J42") (pin "1") (pinfunction "1_1") (pintype "passive"))
      (node (ref "J42") (pin "10") (pinfunction "10_10") (pintype "passive"))
      (node (ref "J42") (pin "11") (pinfunction "11_11") (pintype "passive"))
      (node (ref "J42") (pin "12") (pinfunction "12_12") (pintype "passive"))
      (node (ref "J42") (pin "13") (pinfunction "13_13") (pintype "passive"))
      (node (ref "J42") (pin "14") (pinfunction "14_14") (pintype "passive"))
      (node (ref "J42") (pin "15") (pinfunction "15_15") (pintype "passive"))
      (node (ref "J42") (pin "16") (pinfunction "16_16") (pintype "passive"))
      (node (ref "J42") (pin "17") (pinfunction "17_17") (pintype "passive"))
      (node (ref "J42") (pin "18") (pinfunction "18_18") (pintype "passive"))
      (node (ref "J42") (pin "19") (pinfunction "19_19") (pintype "passive"))
      (node (ref "J42") (pin "2") (pinfunction "2_2") (pintype "passive"))
      (node (ref "J42") (pin "3") (pinfunction "3_3") (pintype "passive"))
      (node (ref "J42") (pin "4") (pinfunction "4_4") (pintype "passive"))
      (node (ref "J42") (pin "5") (pinfunction "5_5") (pintype "passive"))
      (node (ref "J42") (pin "6") (pinfunction "6_6") (pintype "passive"))
      (node (ref "J42") (pin "7") (pinfunction "7_7") (pintype "passive"))
      (node (ref "J42") (pin "8") (pinfunction "8_8") (pintype "passive"))
      (node (ref "J42") (pin "9") (pinfunction "9_9") (pintype "passive"))
      (node (ref "J43") (pin "1") (pinfunction "1_1") (pintype "passive"))
      (node (ref "J43") (pin "10") (pinfunction "10_10") (pintype "passive"))
      (node (ref "J43") (pin "11") (pinfunction "11_11") (pintype "passive"))
      (node (ref "J43") (pin "12") (pinfunction "12_12") (pintype "passive"))
      (node (ref "J43") (pin "13") (pinfunction "13_13") (pintype "passive"))
      (node (ref "J43") (pin "14") (pinfunction "14_14") (pintype "passive"))
      (node (ref "J43") (pin "15") (pinfunction "15_15") (pintype "passive"))
      (node (ref "J43") (pin "16") (pinfunction "16_16") (pintype "passive"))
      (node (ref "J43") (pin "17") (pinfunction "17_17") (pintype "passive"))
      (node (ref "J43") (pin "18") (pinfunction "18_18") (pintype "passive"))
      (node (ref "J43") (pin "19") (pinfunction "19_19") (pintype "passive"))
      (node (ref "J43") (pin "2") (pinfunction "2_2") (pintype "passive"))
      (node (ref "J43") (pin "3") (pinfunction "3_3") (pintype "passive"))
      (node (ref "J43") (pin "4") (pinfunction "4_4") (pintype "passive"))
      (node (ref "J43") (pin "5") (pinfunction "5_5") (pintype "passive"))
      (node (ref "J43") (pin "6") (pinfunction "6_6") (pintype "passive"))
      (node (ref "J43") (pin "7") (pinfunction "7_7") (pintype "passive"))
      (node (ref "J43") (pin "8") (pinfunction "8_8") (pintype "passive"))
      (node (ref "J43") (pin "9") (pinfunction "9_9") (pintype "passive"))
    )
    (net (code "17") (name "Net-(J44-Pad1)") (class "Default")
      (node (ref "J44") (pin "1") (pinfunction "1_1") (pintype "passive"))
      (node (ref "J44") (pin "10") (pinfunction "10_10") (pintype "passive"))
      (node (ref "J44") (pin "11") (pinfunction "11_11") (pintype "passive"))
      (node (ref "J44") (pin "12") (pinfunction "12_12") (pintype "passive"))
      (node (ref "J44") (pin "13") (pinfunction "13_13") (pintype "passive"))
      (node (ref "J44") (pin "14") (pinfunction "14_14") (pintype "passive"))
      (node (ref "J44") (pin "15") (pinfunction "15_15") (pintype "passive"))
      (node (ref "J44") (pin "16") (pinfunction "16_16") (pintype "passive"))
      (node (ref "J44") (pin "17") (pinfunction "17_17") (pintype "passive"))
      (node (ref "J44") (pin "18") (pinfunction "18_18") (pintype "passive"))
      (node (ref "J44") (pin "19") (pinfunction "19_19") (pintype "passive"))
      (node (ref "J44") (pin "2") (pinfunction "2_2") (pintype "passive"))
      (node (ref "J44") (pin "3") (pinfunction "3_3") (pintype "passive"))
      (node (ref "J44") (pin "4") (pinfunction "4_4") (pintype "passive"))
      (node (ref "J44") (pin "5") (pinfunction "5_5") (pintype "passive"))
      (node (ref "J44") (pin "6") (pinfunction "6_6") (pintype "passive"))
      (node (ref "J44") (pin "7") (pinfunction "7_7") (pintype "passive"))
      (node (ref "J44") (pin "8") (pinfunction "8_8") (pintype "passive"))
      (node (ref "J44") (pin "9") (pinfunction "9_9") (pintype "passive"))
      (node (ref "J45") (pin "1") (pinfunction "1_1") (pintype "passive"))
      (node (ref "J45") (pin "10") (pinfunction "10_10") (pintype "passive"))
      (node (ref "J45") (pin "11") (pinfunction "11_11") (pintype "passive"))
      (node (ref "J45") (pin "12") (pinfunction "12_12") (pintype "passive"))
      (node (ref "J45") (pin "13") (pinfunction "13_13") (pintype "passive"))
      (node (ref "J45") (pin "14") (pinfunction "14_14") (pintype "passive"))
      (node (ref "J45") (pin "15") (pinfunction "15_15") (pintype "passive"))
      (node (ref "J45") (pin "16") (pinfunction "16_16") (pintype "passive"))
      (node (ref "J45") (pin "17") (pinfunction "17_17") (pintype "passive"))
      (node (ref "J45") (pin "18") (pinfunction "18_18") (pintype "passive"))
      (node (ref "J45") (pin "19") (pinfunction "19_19") (pintype "passive"))
      (node (ref "J45") (pin "2") (pinfunction "2_2") (pintype "passive"))
      (node (ref "J45") (pin "3") (pinfunction "3_3") (pintype "passive"))
      (node (ref "J45") (pin "4") (pinfunction "4_4") (pintype "passive"))
      (node (ref "J45") (pin "5") (pinfunction "5_5") (pintype "passive"))
      (node (ref "J45") (pin "6") (pinfunction "6_6") (pintype "passive"))
      (node (ref "J45") (pin "7") (pinfunction "7_7") (pintype "passive"))
      (node (ref "J45") (pin "8") (pinfunction "8_8") (pintype "passive"))
      (node (ref "J45") (pin "9") (pinfunction "9_9") (pintype "passive"))
    )
    (net (code "18") (name "Net-(J46-Pad1)") (class "Default")
      (node (ref "J46") (pin "1") (pinfunction "1_1") (pintype "passive"))
      (node (ref "J46") (pin "10") (pinfunction "10_10") (pintype "passive"))
      (node (ref "J46") (pin "11") (pinfunction "11_11") (pintype "passive"))
      (node (ref "J46") (pin "12") (pinfunction "12_12") (pintype "passive"))
      (node (ref "J46") (pin "13") (pinfunction "13_13") (pintype "passive"))
      (node (ref "J46") (pin "14") (pinfunction "14_14") (pintype "passive"))
      (node (ref "J46") (pin "15") (pinfunction "15_15") (pintype "passive"))
      (node (ref "J46") (pin "16") (pinfunction "16_16") (pintype "passive"))
      (node (ref "J46") (pin "17") (pinfunction "17_17") (pintype "passive"))
      (node (ref "J46") (pin "18") (pinfunction "18_18") (pintype "passive"))
      (node (ref "J46") (pin "19") (pinfunction "19_19") (pintype "passive"))
      (node (ref "J46") (pin "2") (pinfunction "2_2") (pintype "passive"))
      (node (ref "J46") (pin "3") (pinfunction "3_3") (pintype "passive"))
      (node (ref "J46") (pin "4") (pinfunction "4_4") (pintype "passive"))
      (node (ref "J46") (pin "5") (pinfunction "5_5") (pintype "passive"))
      (node (ref "J46") (pin "6") (pinfunction "6_6") (pintype "passive"))
      (node (ref "J46") (pin "7") (pinfunction "7_7") (pintype "passive"))
      (node (ref "J46") (pin "8") (pinfunction "8_8") (pintype "passive"))
      (node (ref "J46") (pin "9") (pinfunction "9_9") (pintype "passive"))
      (node (ref "J47") (pin "1") (pinfunction "1_1") (pintype "passive"))
      (node (ref "J47") (pin "10") (pinfunction "10_10") (pintype "passive"))
      (node (ref "J47") (pin "11") (pinfunction "11_11") (pintype "passive"))
      (node (ref "J47") (pin "12") (pinfunction "12_12") (pintype "passive"))
      (node (ref "J47") (pin "13") (pinfunction "13_13") (pintype "passive"))
      (node (ref "J47") (pin "14") (pinfunction "14_14") (pintype "passive"))
      (node (ref "J47") (pin "15") (pinfunction "15_15") (pintype "passive"))
      (node (ref "J47") (pin "16") (pinfunction "16_16") (pintype "passive"))
      (node (ref "J47") (pin "17") (pinfunction "17_17") (pintype "passive"))
      (node (ref "J47") (pin "18") (pinfunction "18_18") (pintype "passive"))
      (node (ref "J47") (pin "19") (pinfunction "19_19") (pintype "passive"))
      (node (ref "J47") (pin "2") (pinfunction "2_2") (pintype "passive"))
      (node (ref "J47") (pin "3") (pinfunction "3_3") (pintype "passive"))
      (node (ref "J47") (pin "4") (pinfunction "4_4") (pintype "passive"))
      (node (ref "J47") (pin "5") (pinfunction "5_5") (pintype "passive"))
      (node (ref "J47") (pin "6") (pinfunction "6_6") (pintype "passive"))
      (node (ref "J47") (pin "7") (pinfunction "7_7") (pintype "passive"))
      (node (ref "J47") (pin "8") (pinfunction "8_8") (pintype "passive"))
      (node (ref "J47") (pin "9") (pinfunction "9_9") (pintype "passive"))
    )
  )
)
